# MB1166.net
KiCad netlist of a schematic drawn in Altium Designer
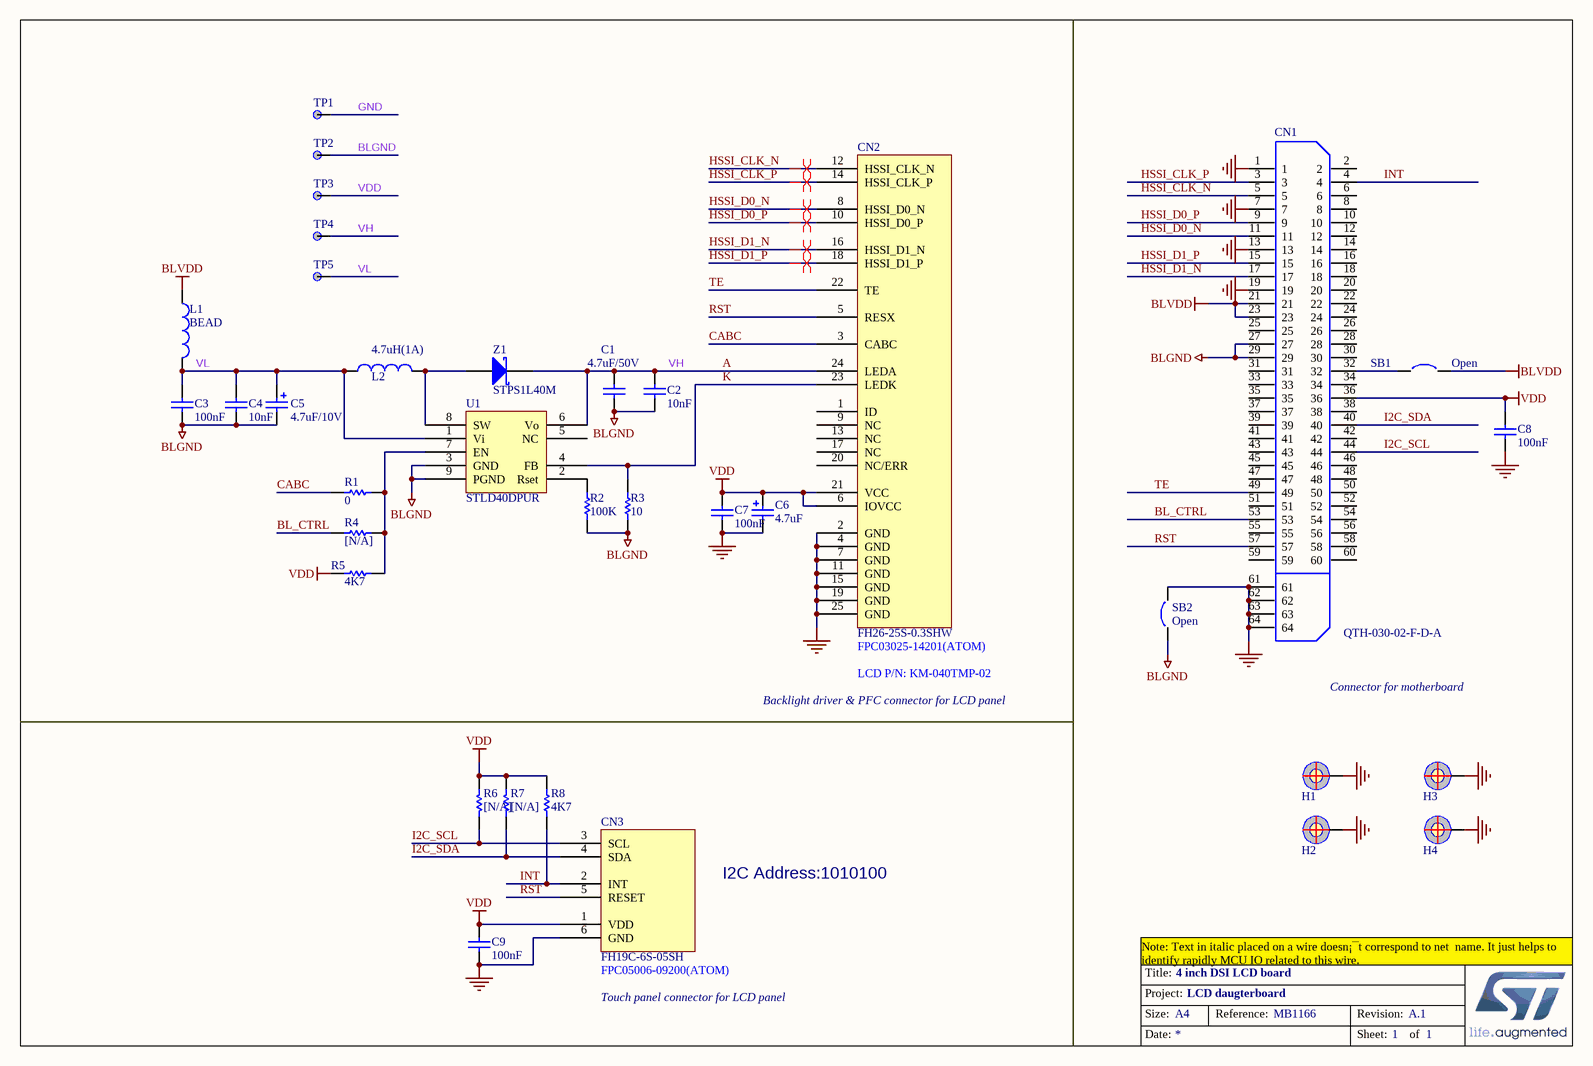
[diagram p0: MB1166.SchDoc]

(export (version "E")
  (design (tool "Eeschema 10.0.6"))
  (components
    (comp (ref "C1")
      (value "4.7uF/50V")
      (footprint "1206C")
      (description "Capacitor")
      (fields (field (name "PUBLISHER") "Altium Limited"))
      (libsource (lib "Miscellaneous Devices") (part "CAP"))
    )
    (comp (ref "C2")
      (value "10nF")
      (footprint "0603C")
      (description "Capacitor")
      (fields (field (name "PUBLISHER") "Altium Limited"))
      (libsource (lib "*") (part "CAP"))
    )
    (comp (ref "C3")
      (value "100nF")
      (footprint "0603C")
      (description "Capacitor")
      (fields (field (name "PUBLISHER") "Altium Limited"))
      (libsource (lib "Miscellaneous Devices") (part "CAP"))
    )
    (comp (ref "C4")
      (value "10nF")
      (footprint "0603C")
      (description "Capacitor")
      (fields (field (name "PUBLISHER") "Altium Limited"))
      (libsource (lib "Miscellaneous Devices") (part "CAP"))
    )
    (comp (ref "C5")
      (value "4.7uF/10V")
      (footprint "1206C")
      (description "Polarized Capacitor (Radial)")
      (fields (field (name "PUBLISHER") "Altium Limited"))
      (libsource (lib "Miscellaneous Devices") (part "Cap Pol1"))
    )
    (comp (ref "C6")
      (value "4.7uF")
      (footprint "TAN-A")
      (description "Polarized Capacitor (Radial)")
      (fields (field (name "PUBLISHER") "Altium Limited"))
      (libsource (lib "Miscellaneous Devices") (part "Cap Pol1"))
    )
    (comp (ref "C7")
      (value "100nF")
      (footprint "0603C")
      (description "Capacitor")
      (fields (field (name "PUBLISHER") "Altium Limited"))
      (libsource (lib "Miscellaneous Devices") (part "CAP"))
    )
    (comp (ref "C8")
      (value "100nF")
      (footprint "0603C")
      (description "Capacitor")
      (fields (field (name "PUBLISHER") "Altium Limited"))
      (libsource (lib "Miscellaneous Devices") (part "CAP"))
    )
    (comp (ref "C9")
      (value "100nF")
      (footprint "0603C")
      (description "Capacitor")
      (fields (field (name "PUBLISHER") "Altium Limited"))
      (libsource (lib "Miscellaneous Devices") (part "CAP"))
    )
    (comp (ref "CN1")
      (value "QTH-030-02-F-D-A")
      (footprint "QTH-030-02-F-D-A")
      (description "HIGH SPEED TERMINAL STRIP, .5mm PITCH, 60 PINS.")
      (fields (field (name "MANUFACTURER") "SAMTEC") (field (name "CREATED") "16 FEB 2013 - WENDY XIN"))
      (libsource (lib "MB1165") (part "QTH-030-02-F-D-A"))
    )
    (comp (ref "CN2")
      (value "FH26-25S-0.3SHW")
      (footprint "FPC25_FPC03025-1420")
      (libsource (lib "MB1166") (part "FH26-25S-0.3SHW"))
    )
    (comp (ref "CN3")
      (value "FH19C-6S-05SH")
      (footprint "FH19C-6S-0R5Sh_FPC_CPT")
      (libsource (lib "MB1166") (part "FH19C-6S-05SH"))
    )
    (comp (ref "H1")
      (value "POSITION HOLE")
      (footprint "HOLE_C9D4R5")
      (libsource (lib "mb1045") (part "POSITION HOLE"))
    )
    (comp (ref "H2")
      (value "POSITION HOLE")
      (footprint "HOLE_C9D4R5")
      (libsource (lib "mb1045") (part "POSITION HOLE"))
    )
    (comp (ref "H3")
      (value "POSITION HOLE")
      (footprint "HOLE_C9D4R5")
      (libsource (lib "mb1045") (part "POSITION HOLE"))
    )
    (comp (ref "H4")
      (value "POSITION HOLE")
      (footprint "HOLE_C9D4R5")
      (libsource (lib "mb1045") (part "POSITION HOLE"))
    )
    (comp (ref "L1")
      (value "BEAD")
      (footprint "0603L")
      (description "Inductor")
      (fields (field (name "PUBLISHER") "Altium Limited"))
      (libsource (lib "Miscellaneous Devices") (part "Inductor"))
    )
    (comp (ref "L2")
      (value "4.7uH(1A)")
      (footprint "1210L")
      (description "Inductor")
      (fields (field (name "PUBLISHER") "Altium Limited"))
      (libsource (lib "Miscellaneous Devices") (part "Inductor"))
    )
    (comp (ref "R1")
      (value "0")
      (footprint "0603R")
      (description "Resistor")
      (fields (field (name "PUBLISHER") "Altium Limited"))
      (libsource (lib "Miscellaneous Devices") (part "Res1"))
    )
    (comp (ref "R2")
      (value "100K")
      (footprint "0603R")
      (description "Resistor")
      (fields (field (name "PUBLISHER") "Altium Limited"))
      (libsource (lib "Miscellaneous Devices") (part "Res1"))
    )
    (comp (ref "R3")
      (value "10")
      (footprint "0603R")
      (description "Resistor")
      (fields (field (name "PUBLISHER") "Altium Limited"))
      (libsource (lib "Miscellaneous Devices") (part "Res1"))
    )
    (comp (ref "R4")
      (value "[N/A]")
      (footprint "0603R")
      (description "Resistor")
      (fields (field (name "PUBLISHER") "Altium Limited"))
      (libsource (lib "Miscellaneous Devices") (part "Res1"))
    )
    (comp (ref "R5")
      (value "4K7")
      (footprint "0603R")
      (description "Resistor")
      (fields (field (name "PUBLISHER") "Altium Limited"))
      (libsource (lib "Miscellaneous Devices") (part "Res1"))
    )
    (comp (ref "R6")
      (value "[N/A]")
      (footprint "0603R")
      (description "Resistor")
      (fields (field (name "PUBLISHER") "Altium Limited"))
      (libsource (lib "*") (part "Res1"))
    )
    (comp (ref "R7")
      (value "[N/A]")
      (footprint "0603R")
      (description "Resistor")
      (fields (field (name "PUBLISHER") "Altium Limited"))
      (libsource (lib "*") (part "Res1"))
    )
    (comp (ref "R8")
      (value "4K7")
      (footprint "0603R")
      (description "Resistor")
      (fields (field (name "PUBLISHER") "Altium Limited"))
      (libsource (lib "*") (part "Res1"))
    )
    (comp (ref "SB1")
      (value "Open")
      (footprint "SB_0603")
      (description "Circuit Breaker")
      (fields (field (name "PUBLISHER") "Altium Limited"))
      (libsource (lib "MB1165") (part "Circuit Breaker"))
    )
    (comp (ref "SB2")
      (value "Open")
      (footprint "SB_0603")
      (description "Circuit Breaker")
      (fields (field (name "PUBLISHER") "Altium Limited"))
      (libsource (lib "MB1165") (part "Circuit Breaker"))
    )
    (comp (ref "TP1") (value "~") (footprint "TP") (libsource (lib "*") (part "TP")))
    (comp (ref "TP2") (value "~") (footprint "TP") (libsource (lib "*") (part "TP")))
    (comp (ref "TP3") (value "~") (footprint "TP") (libsource (lib "*") (part "TP")))
    (comp (ref "TP4") (value "~") (footprint "TP") (libsource (lib "*") (part "TP")))
    (comp (ref "TP5") (value "~") (footprint "TP") (libsource (lib "*") (part "TP")))
    (comp (ref "U1")
      (value "STLD40DPUR")
      (footprint "SON8_0R65_3X3")
      (libsource (lib "3.2LCD_daughterboard") (part "STLD40DPMR"))
    )
    (comp (ref "Z1")
      (value "STPS1L40M")
      (footprint "DO-216AA")
      (description "Schottky Diode")
      (fields (field (name "PUBLISHER") "Altium Limited"))
      (libsource (lib "Miscellaneous Devices") (part "D Schottky"))
    )
  )
  (nets
    (net (code "1") (name "/A") (class "Default")
      (node (ref "C1") (pin "1") (pinfunction "1_1") (pintype "passive"))
      (node (ref "C2") (pin "2") (pinfunction "2_2") (pintype "passive"))
      (node (ref "CN2") (pin "24") (pinfunction "LEDA_24") (pintype "passive"))
      (node (ref "TP4") (pin "1") (pinfunction "1_1") (pintype "passive"))
      (node (ref "U1") (pin "6") (pinfunction "Vo_6") (pintype "passive"))
      (node (ref "Z1") (pin "2") (pinfunction "K_2") (pintype "passive"))
    )
    (net (code "2") (name "/BL_CTRL") (class "Default")
      (node (ref "CN1") (pin "53") (pinfunction "53_53") (pintype "passive"))
      (node (ref "R4") (pin "2") (pinfunction "2_2") (pintype "passive"))
    )
    (net (code "3") (name "/CABC") (class "Default")
      (node (ref "CN2") (pin "3") (pinfunction "CABC_3") (pintype "passive"))
      (node (ref "R1") (pin "2") (pinfunction "2_2") (pintype "passive"))
    )
    (net (code "4") (name "/HSSI_CLK_N") (class "Default")
      (node (ref "CN1") (pin "5") (pinfunction "5_5") (pintype "passive"))
      (node (ref "CN2") (pin "12") (pinfunction "HSSI_CLK_N_12") (pintype "passive"))
    )
    (net (code "5") (name "/HSSI_CLK_P") (class "Default")
      (node (ref "CN1") (pin "3") (pinfunction "3_3") (pintype "passive"))
      (node (ref "CN2") (pin "14") (pinfunction "HSSI_CLK_P_14") (pintype "passive"))
    )
    (net (code "6") (name "/HSSI_D0_N") (class "Default")
      (node (ref "CN1") (pin "11") (pinfunction "11_11") (pintype "passive"))
      (node (ref "CN2") (pin "8") (pinfunction "HSSI_D0_N_8") (pintype "passive"))
    )
    (net (code "7") (name "/HSSI_D0_P") (class "Default")
      (node (ref "CN1") (pin "9") (pinfunction "9_9") (pintype "passive"))
      (node (ref "CN2") (pin "10") (pinfunction "HSSI_D0_P_10") (pintype "passive"))
    )
    (net (code "8") (name "/HSSI_D1_N") (class "Default")
      (node (ref "CN1") (pin "17") (pinfunction "17_17") (pintype "passive"))
      (node (ref "CN2") (pin "16") (pinfunction "HSSI_D1_N_16") (pintype "passive"))
    )
    (net (code "9") (name "/HSSI_D1_P") (class "Default")
      (node (ref "CN1") (pin "15") (pinfunction "15_15") (pintype "passive"))
      (node (ref "CN2") (pin "18") (pinfunction "HSSI_D1_P_18") (pintype "passive"))
    )
    (net (code "10") (name "/I2C_SCL") (class "Default")
      (node (ref "CN1") (pin "44") (pinfunction "44_44") (pintype "passive"))
      (node (ref "CN3") (pin "3") (pinfunction "SCL_3") (pintype "passive"))
      (node (ref "R6") (pin "1") (pinfunction "1_1") (pintype "passive"))
    )
    (net (code "11") (name "/I2C_SDA") (class "Default")
      (node (ref "CN1") (pin "40") (pinfunction "40_40") (pintype "passive"))
      (node (ref "CN3") (pin "4") (pinfunction "SDA_4") (pintype "passive"))
      (node (ref "R7") (pin "1") (pinfunction "1_1") (pintype "passive"))
    )
    (net (code "12") (name "/INT") (class "Default")
      (node (ref "CN1") (pin "4") (pinfunction "4_4") (pintype "passive"))
      (node (ref "CN3") (pin "2") (pinfunction "INT_2") (pintype "passive"))
      (node (ref "R8") (pin "2") (pinfunction "2_2") (pintype "passive"))
    )
    (net (code "13") (name "/K") (class "Default")
      (node (ref "CN2") (pin "23") (pinfunction "LEDK_23") (pintype "passive"))
      (node (ref "R3") (pin "2") (pinfunction "2_2") (pintype "passive"))
      (node (ref "U1") (pin "4") (pinfunction "FB_4") (pintype "passive"))
    )
    (net (code "14") (name "/RST") (class "Default")
      (node (ref "CN1") (pin "57") (pinfunction "57_57") (pintype "passive"))
      (node (ref "CN2") (pin "5") (pinfunction "RESX_5") (pintype "passive"))
      (node (ref "CN3") (pin "5") (pinfunction "RESET_5") (pintype "passive"))
    )
    (net (code "15") (name "/TE") (class "Default")
      (node (ref "CN1") (pin "49") (pinfunction "49_49") (pintype "passive"))
      (node (ref "CN2") (pin "22") (pinfunction "TE_22") (pintype "passive"))
    )
    (net (code "16") (name "/VL") (class "Default")
      (node (ref "C3") (pin "2") (pinfunction "2_2") (pintype "passive"))
      (node (ref "C4") (pin "2") (pinfunction "2_2") (pintype "passive"))
      (node (ref "C5") (pin "1") (pinfunction "1_1") (pintype "passive"))
      (node (ref "L1") (pin "2") (pinfunction "2_2") (pintype "passive"))
      (node (ref "L2") (pin "1") (pinfunction "1_1") (pintype "passive"))
      (node (ref "TP5") (pin "1") (pinfunction "1_1") (pintype "passive"))
      (node (ref "U1") (pin "1") (pinfunction "Vi_1") (pintype "passive"))
    )
    (net (code "17") (name "BLGND") (class "Default")
      (node (ref "C1") (pin "2") (pinfunction "2_2") (pintype "passive"))
      (node (ref "C2") (pin "1") (pinfunction "1_1") (pintype "passive"))
      (node (ref "C3") (pin "1") (pinfunction "1_1") (pintype "passive"))
      (node (ref "C4") (pin "1") (pinfunction "1_1") (pintype "passive"))
      (node (ref "C5") (pin "2") (pinfunction "2_2") (pintype "passive"))
      (node (ref "CN1") (pin "27") (pinfunction "27_27") (pintype "passive"))
      (node (ref "CN1") (pin "29") (pinfunction "29_29") (pintype "passive"))
      (node (ref "R2") (pin "2") (pinfunction "2_2") (pintype "passive"))
      (node (ref "R3") (pin "1") (pinfunction "1_1") (pintype "passive"))
      (node (ref "SB2") (pin "1") (pinfunction "1_1") (pintype "passive"))
      (node (ref "TP2") (pin "1") (pinfunction "1_1") (pintype "passive"))
      (node (ref "U1") (pin "3") (pinfunction "GND_3") (pintype "passive"))
      (node (ref "U1") (pin "9") (pinfunction "PGND_9") (pintype "passive"))
    )
    (net (code "18") (name "BLVDD") (class "Default")
      (node (ref "CN1") (pin "21") (pinfunction "21_21") (pintype "passive"))
      (node (ref "CN1") (pin "23") (pinfunction "23_23") (pintype "passive"))
      (node (ref "L1") (pin "1") (pinfunction "1_1") (pintype "passive"))
      (node (ref "SB1") (pin "2") (pinfunction "2_2") (pintype "passive"))
    )
    (net (code "19") (name "GND") (class "Default")
      (node (ref "C6") (pin "2") (pinfunction "2_2") (pintype "passive"))
      (node (ref "C7") (pin "1") (pinfunction "1_1") (pintype "passive"))
      (node (ref "C8") (pin "1") (pinfunction "1_1") (pintype "passive"))
      (node (ref "C9") (pin "1") (pinfunction "1_1") (pintype "passive"))
      (node (ref "CN1") (pin "1") (pinfunction "1_1") (pintype "passive"))
      (node (ref "CN1") (pin "13") (pinfunction "13_13") (pintype "passive"))
      (node (ref "CN1") (pin "19") (pinfunction "19_19") (pintype "passive"))
      (node (ref "CN1") (pin "61") (pinfunction "61_61") (pintype "passive"))
      (node (ref "CN1") (pin "62") (pinfunction "62_62") (pintype "passive"))
      (node (ref "CN1") (pin "63") (pinfunction "63_63") (pintype "passive"))
      (node (ref "CN1") (pin "64") (pinfunction "64_64") (pintype "passive"))
      (node (ref "CN1") (pin "7") (pinfunction "7_7") (pintype "passive"))
      (node (ref "CN2") (pin "11") (pinfunction "GND_11") (pintype "passive"))
      (node (ref "CN2") (pin "15") (pinfunction "GND_15") (pintype "passive"))
      (node (ref "CN2") (pin "19") (pinfunction "GND_19") (pintype "passive"))
      (node (ref "CN2") (pin "2") (pinfunction "GND_2") (pintype "passive"))
      (node (ref "CN2") (pin "25") (pinfunction "GND_25") (pintype "passive"))
      (node (ref "CN2") (pin "4") (pinfunction "GND_4") (pintype "passive"))
      (node (ref "CN2") (pin "7") (pinfunction "GND_7") (pintype "passive"))
      (node (ref "CN3") (pin "6") (pinfunction "GND_6") (pintype "passive"))
      (node (ref "H1") (pin "1") (pinfunction "1_1") (pintype "passive"))
      (node (ref "H2") (pin "1") (pinfunction "1_1") (pintype "passive"))
      (node (ref "H3") (pin "1") (pinfunction "1_1") (pintype "passive"))
      (node (ref "H4") (pin "1") (pinfunction "1_1") (pintype "passive"))
      (node (ref "SB2") (pin "2") (pinfunction "2_2") (pintype "passive"))
      (node (ref "TP1") (pin "1") (pinfunction "1_1") (pintype "passive"))
    )
    (net (code "20") (name "Net-(CN1-Pad32)") (class "Default")
      (node (ref "CN1") (pin "32") (pinfunction "32_32") (pintype "passive"))
      (node (ref "SB1") (pin "1") (pinfunction "1_1") (pintype "passive"))
    )
    (net (code "21") (name "Net-(U1-EN)") (class "Default")
      (node (ref "R1") (pin "1") (pinfunction "1_1") (pintype "passive"))
      (node (ref "R4") (pin "1") (pinfunction "1_1") (pintype "passive"))
      (node (ref "R5") (pin "1") (pinfunction "1_1") (pintype "passive"))
      (node (ref "U1") (pin "7") (pinfunction "EN_7") (pintype "passive"))
    )
    (net (code "22") (name "Net-(U1-Rset)") (class "Default")
      (node (ref "R2") (pin "1") (pinfunction "1_1") (pintype "passive"))
      (node (ref "U1") (pin "2") (pinfunction "Rset_2") (pintype "passive"))
    )
    (net (code "23") (name "Net-(U1-SW)") (class "Default")
      (node (ref "L2") (pin "2") (pinfunction "2_2") (pintype "passive"))
      (node (ref "U1") (pin "8") (pinfunction "SW_8") (pintype "passive"))
      (node (ref "Z1") (pin "1") (pinfunction "A_1") (pintype "passive"))
    )
    (net (code "24") (name "VDD") (class "Default")
      (node (ref "C6") (pin "1") (pinfunction "1_1") (pintype "passive"))
      (node (ref "C7") (pin "2") (pinfunction "2_2") (pintype "passive"))
      (node (ref "C8") (pin "2") (pinfunction "2_2") (pintype "passive"))
      (node (ref "C9") (pin "2") (pinfunction "2_2") (pintype "passive"))
      (node (ref "CN1") (pin "36") (pinfunction "36_36") (pintype "passive"))
      (node (ref "CN2") (pin "21") (pinfunction "VCC_21") (pintype "passive"))
      (node (ref "CN2") (pin "6") (pinfunction "IOVCC_6") (pintype "passive"))
      (node (ref "CN3") (pin "1") (pinfunction "VDD_1") (pintype "passive"))
      (node (ref "R5") (pin "2") (pinfunction "2_2") (pintype "passive"))
      (node (ref "R6") (pin "2") (pinfunction "2_2") (pintype "passive"))
      (node (ref "R7") (pin "2") (pinfunction "2_2") (pintype "passive"))
      (node (ref "R8") (pin "1") (pinfunction "1_1") (pintype "passive"))
      (node (ref "TP3") (pin "1") (pinfunction "1_1") (pintype "passive"))
    )
    (net (code "25") (name "unconnected-(CN1-Pad2)") (class "Default")
      (node (ref "CN1") (pin "2") (pinfunction "2_2") (pintype "passive"))
    )
    (net (code "26") (name "unconnected-(CN1-Pad6)") (class "Default")
      (node (ref "CN1") (pin "6") (pinfunction "6_6") (pintype "passive"))
    )
    (net (code "27") (name "unconnected-(CN1-Pad8)") (class "Default")
      (node (ref "CN1") (pin "8") (pinfunction "8_8") (pintype "passive"))
    )
    (net (code "28") (name "unconnected-(CN1-Pad10)") (class "Default")
      (node (ref "CN1") (pin "10") (pinfunction "10_10") (pintype "passive"))
    )
    (net (code "29") (name "unconnected-(CN1-Pad12)") (class "Default")
      (node (ref "CN1") (pin "12") (pinfunction "12_12") (pintype "passive"))
    )
    (net (code "30") (name "unconnected-(CN1-Pad14)") (class "Default")
      (node (ref "CN1") (pin "14") (pinfunction "14_14") (pintype "passive"))
    )
    (net (code "31") (name "unconnected-(CN1-Pad16)") (class "Default")
      (node (ref "CN1") (pin "16") (pinfunction "16_16") (pintype "passive"))
    )
    (net (code "32") (name "unconnected-(CN1-Pad18)") (class "Default")
      (node (ref "CN1") (pin "18") (pinfunction "18_18") (pintype "passive"))
    )
    (net (code "33") (name "unconnected-(CN1-Pad20)") (class "Default")
      (node (ref "CN1") (pin "20") (pinfunction "20_20") (pintype "passive"))
    )
    (net (code "34") (name "unconnected-(CN1-Pad22)") (class "Default")
      (node (ref "CN1") (pin "22") (pinfunction "22_22") (pintype "passive"))
    )
    (net (code "35") (name "unconnected-(CN1-Pad24)") (class "Default")
      (node (ref "CN1") (pin "24") (pinfunction "24_24") (pintype "passive"))
    )
    (net (code "36") (name "unconnected-(CN1-Pad25)") (class "Default")
      (node (ref "CN1") (pin "25") (pinfunction "25_25") (pintype "passive"))
    )
    (net (code "37") (name "unconnected-(CN1-Pad26)") (class "Default")
      (node (ref "CN1") (pin "26") (pinfunction "26_26") (pintype "passive"))
    )
    (net (code "38") (name "unconnected-(CN1-Pad28)") (class "Default")
      (node (ref "CN1") (pin "28") (pinfunction "28_28") (pintype "passive"))
    )
    (net (code "39") (name "unconnected-(CN1-Pad30)") (class "Default")
      (node (ref "CN1") (pin "30") (pinfunction "30_30") (pintype "passive"))
    )
    (net (code "40") (name "unconnected-(CN1-Pad31)") (class "Default")
      (node (ref "CN1") (pin "31") (pinfunction "31_31") (pintype "passive"))
    )
    (net (code "41") (name "unconnected-(CN1-Pad33)") (class "Default")
      (node (ref "CN1") (pin "33") (pinfunction "33_33") (pintype "passive"))
    )
    (net (code "42") (name "unconnected-(CN1-Pad34)") (class "Default")
      (node (ref "CN1") (pin "34") (pinfunction "34_34") (pintype "passive"))
    )
    (net (code "43") (name "unconnected-(CN1-Pad35)") (class "Default")
      (node (ref "CN1") (pin "35") (pinfunction "35_35") (pintype "passive"))
    )
    (net (code "44") (name "unconnected-(CN1-Pad37)") (class "Default")
      (node (ref "CN1") (pin "37") (pinfunction "37_37") (pintype "passive"))
    )
    (net (code "45") (name "unconnected-(CN1-Pad38)") (class "Default")
      (node (ref "CN1") (pin "38") (pinfunction "38_38") (pintype "passive"))
    )
    (net (code "46") (name "unconnected-(CN1-Pad39)") (class "Default")
      (node (ref "CN1") (pin "39") (pinfunction "39_39") (pintype "passive"))
    )
    (net (code "47") (name "unconnected-(CN1-Pad41)") (class "Default")
      (node (ref "CN1") (pin "41") (pinfunction "41_41") (pintype "passive"))
    )
    (net (code "48") (name "unconnected-(CN1-Pad42)") (class "Default")
      (node (ref "CN1") (pin "42") (pinfunction "42_42") (pintype "passive"))
    )
    (net (code "49") (name "unconnected-(CN1-Pad43)") (class "Default")
      (node (ref "CN1") (pin "43") (pinfunction "43_43") (pintype "passive"))
    )
    (net (code "50") (name "unconnected-(CN1-Pad45)") (class "Default")
      (node (ref "CN1") (pin "45") (pinfunction "45_45") (pintype "passive"))
    )
    (net (code "51") (name "unconnected-(CN1-Pad46)") (class "Default")
      (node (ref "CN1") (pin "46") (pinfunction "46_46") (pintype "passive"))
    )
    (net (code "52") (name "unconnected-(CN1-Pad47)") (class "Default")
      (node (ref "CN1") (pin "47") (pinfunction "47_47") (pintype "passive"))
    )
    (net (code "53") (name "unconnected-(CN1-Pad48)") (class "Default")
      (node (ref "CN1") (pin "48") (pinfunction "48_48") (pintype "passive"))
    )
    (net (code "54") (name "unconnected-(CN1-Pad50)") (class "Default")
      (node (ref "CN1") (pin "50") (pinfunction "50_50") (pintype "passive"))
    )
    (net (code "55") (name "unconnected-(CN1-Pad51)") (class "Default")
      (node (ref "CN1") (pin "51") (pinfunction "51_51") (pintype "passive"))
    )
    (net (code "56") (name "unconnected-(CN1-Pad52)") (class "Default")
      (node (ref "CN1") (pin "52") (pinfunction "52_52") (pintype "passive"))
    )
    (net (code "57") (name "unconnected-(CN1-Pad54)") (class "Default")
      (node (ref "CN1") (pin "54") (pinfunction "54_54") (pintype "passive"))
    )
    (net (code "58") (name "unconnected-(CN1-Pad55)") (class "Default")
      (node (ref "CN1") (pin "55") (pinfunction "55_55") (pintype "passive"))
    )
    (net (code "59") (name "unconnected-(CN1-Pad56)") (class "Default")
      (node (ref "CN1") (pin "56") (pinfunction "56_56") (pintype "passive"))
    )
    (net (code "60") (name "unconnected-(CN1-Pad58)") (class "Default")
      (node (ref "CN1") (pin "58") (pinfunction "58_58") (pintype "passive"))
    )
    (net (code "61") (name "unconnected-(CN1-Pad59)") (class "Default")
      (node (ref "CN1") (pin "59") (pinfunction "59_59") (pintype "passive"))
    )
    (net (code "62") (name "unconnected-(CN1-Pad60)") (class "Default")
      (node (ref "CN1") (pin "60") (pinfunction "60_60") (pintype "passive"))
    )
    (net (code "63") (name "unconnected-(CN2-ID-Pad1)") (class "Default")
      (node (ref "CN2") (pin "1") (pinfunction "ID_1") (pintype "passive"))
    )
    (net (code "64") (name "unconnected-(CN2-NC-Pad9)") (class "Default")
      (node (ref "CN2") (pin "9") (pinfunction "NC_9") (pintype "passive"))
    )
    (net (code "65") (name "unconnected-(CN2-NC-Pad13)") (class "Default")
      (node (ref "CN2") (pin "13") (pinfunction "NC_13") (pintype "passive"))
    )
    (net (code "66") (name "unconnected-(CN2-NC-Pad17)") (class "Default")
      (node (ref "CN2") (pin "17") (pinfunction "NC_17") (pintype "passive"))
    )
    (net (code "67") (name "unconnected-(CN2-NC{slash}ERR-Pad20)") (class "Default")
      (node (ref "CN2") (pin "20") (pinfunction "NC/ERR_20") (pintype "passive"))
    )
    (net (code "68") (name "unconnected-(U1-NC-Pad5)") (class "Default")
      (node (ref "U1") (pin "5") (pinfunction "NC_5") (pintype "passive"))
    )
  )
)
